# mega_shield.net
KiCad netlist of a schematic drawn in EAGLE
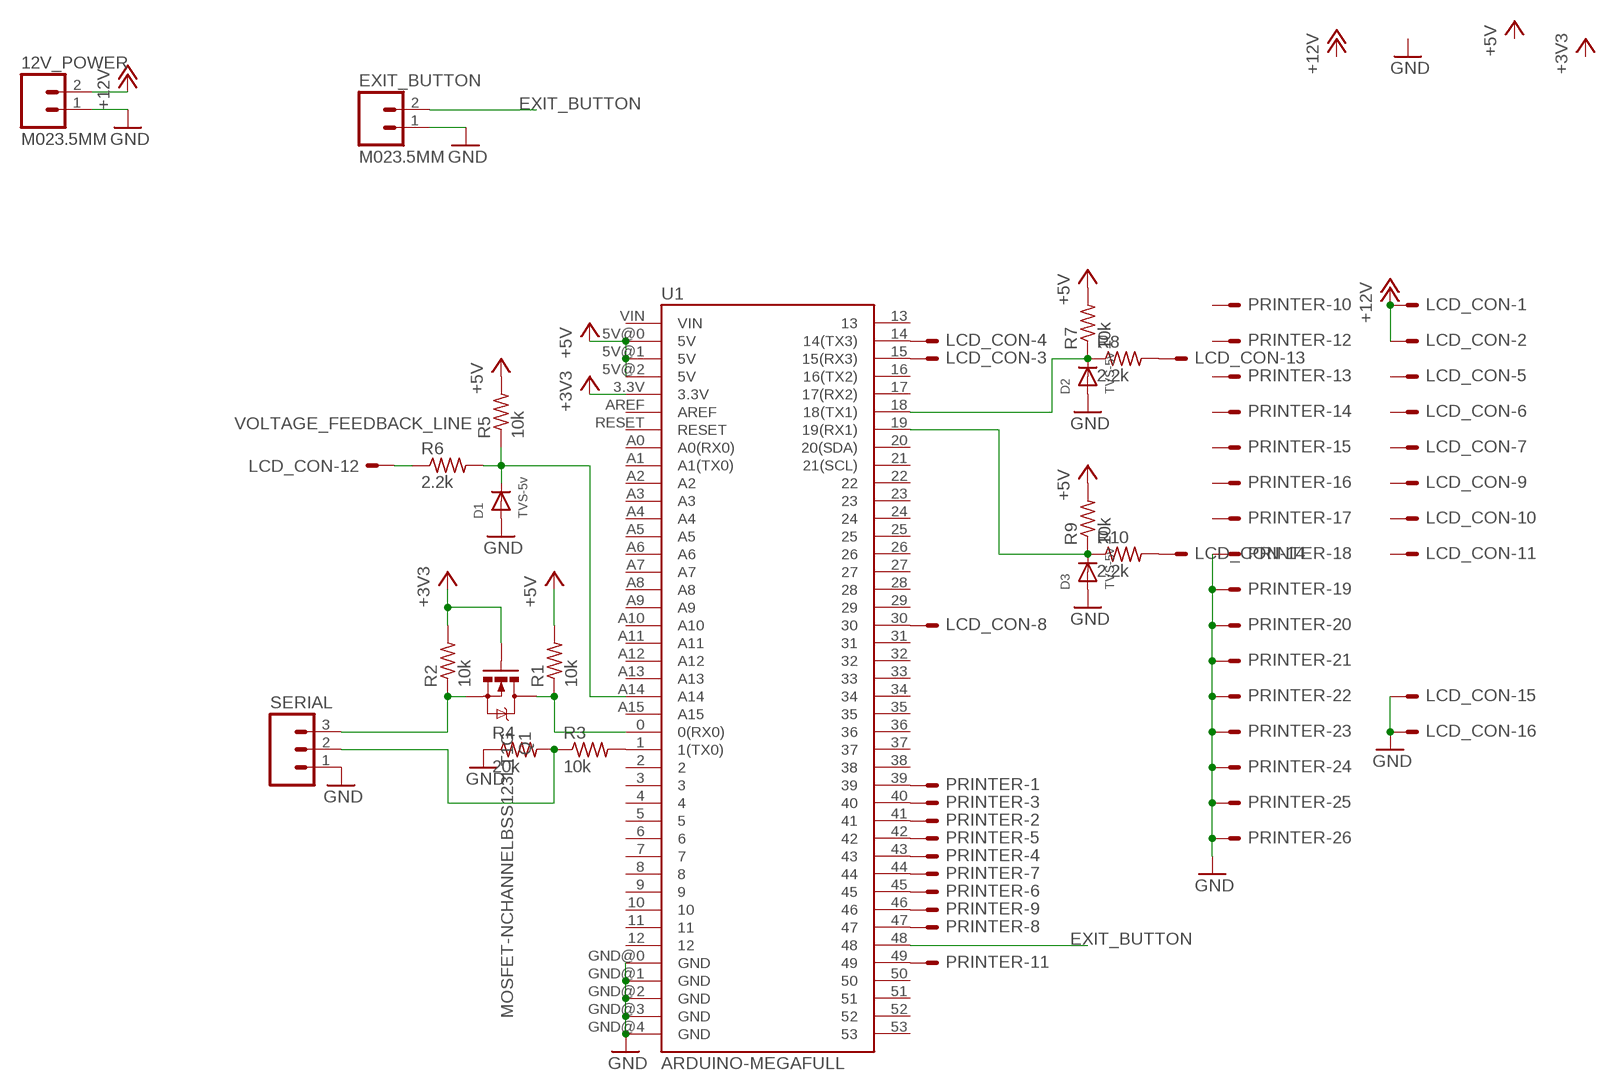
[diagram p0: schematic, sheet 1]

(export (version "E")
  (design (tool "Eeschema 10.0.6"))
  (components
    (comp (ref "12V_POWER")
      (value "M023.5MM")
      (footprint "eagle-import:SCREWTERMINAL-3.5MM-2")
      (libsource (lib "eagle-import") (part "M023.5MM"))
    )
    (comp (ref "D1")
      (value "TVS-5v")
      (footprint "eagle-import:SOD-123")
      (libsource (lib "eagle-import") (part "DIODESOD-123"))
    )
    (comp (ref "D2")
      (value "TVS-5v")
      (footprint "eagle-import:SOD-123")
      (libsource (lib "eagle-import") (part "DIODESOD-123"))
    )
    (comp (ref "D3")
      (value "TVS-5v")
      (footprint "eagle-import:SOD-123")
      (libsource (lib "eagle-import") (part "DIODESOD-123"))
    )
    (comp (ref "EXIT_BUTTON")
      (value "M023.5MM")
      (footprint "eagle-import:SCREWTERMINAL-3.5MM-2")
      (libsource (lib "eagle-import") (part "M023.5MM"))
    )
    (comp (ref "LCD_CON")
      (value "ML16E")
      (footprint "eagle-import:ML16")
      (libsource (lib "eagle-import") (part "ML16?E"))
    )
    (comp (ref "PRINTER")
      (value "ML26E")
      (footprint "eagle-import:ML26")
      (libsource (lib "eagle-import") (part "ML26?E"))
    )
    (comp (ref "Q1")
      (value "MOSFET-NCHANNELBSS123LT1G")
      (footprint "eagle-import:SOT23")
      (libsource (lib "eagle-import") (part "MOSFET-NCHANNELBSS123LT1G"))
    )
    (comp (ref "R1")
      (value "10k")
      (footprint "eagle-import:R0603")
      (libsource (lib "eagle-import") (part "R-US_R0603"))
    )
    (comp (ref "R2")
      (value "10k")
      (footprint "eagle-import:R0603")
      (libsource (lib "eagle-import") (part "R-US_R0603"))
    )
    (comp (ref "R3")
      (value "10k")
      (footprint "eagle-import:R0603")
      (libsource (lib "eagle-import") (part "R-US_R0603"))
    )
    (comp (ref "R4")
      (value "20k")
      (footprint "eagle-import:R0603")
      (libsource (lib "eagle-import") (part "R-US_R0603"))
    )
    (comp (ref "R5")
      (value "10k")
      (footprint "eagle-import:R0603")
      (libsource (lib "eagle-import") (part "R-US_R0603"))
    )
    (comp (ref "R6")
      (value "2.2k")
      (footprint "eagle-import:R0603")
      (libsource (lib "eagle-import") (part "R-US_R0603"))
    )
    (comp (ref "R7")
      (value "10k")
      (footprint "eagle-import:R0603")
      (libsource (lib "eagle-import") (part "R-US_R0603"))
    )
    (comp (ref "R8")
      (value "2.2k")
      (footprint "eagle-import:R0603")
      (libsource (lib "eagle-import") (part "R-US_R0603"))
    )
    (comp (ref "R9")
      (value "10k")
      (footprint "eagle-import:R0603")
      (libsource (lib "eagle-import") (part "R-US_R0603"))
    )
    (comp (ref "R10")
      (value "2.2k")
      (footprint "eagle-import:R0603")
      (libsource (lib "eagle-import") (part "R-US_R0603"))
    )
    (comp (ref "SERIAL")
      (value "M03SCREW")
      (footprint "eagle-import:SCREWTERMINAL-3.5MM-3")
      (libsource (lib "eagle-import") (part "M03SCREW"))
    )
    (comp (ref "U1")
      (value "ARDUINO-MEGAFULL")
      (footprint "eagle-import:ARDUINO_MEGA")
      (libsource (lib "eagle-import") (part "ARDUINO-MEGAFULL"))
    )
  )
  (nets
    (net (code "1") (name "+3V3") (class "Default")
      (node (ref "Q1") (pin "1") (pinfunction "G_1") (pintype "passive"))
      (node (ref "R2") (pin "2") (pinfunction "2_2") (pintype "passive"))
      (node (ref "U1") (pin "3.3V") (pinfunction "3.3V_3.3V") (pintype "bidirectional"))
    )
    (net (code "2") (name "+5V") (class "Default")
      (node (ref "R1") (pin "2") (pinfunction "2_2") (pintype "passive"))
      (node (ref "R5") (pin "2") (pinfunction "2_2") (pintype "passive"))
      (node (ref "R7") (pin "2") (pinfunction "2_2") (pintype "passive"))
      (node (ref "R9") (pin "2") (pinfunction "2_2") (pintype "passive"))
      (node (ref "U1") (pin "5V@0") (pinfunction "5V_5V@0") (pintype "bidirectional"))
      (node (ref "U1") (pin "5V@1") (pinfunction "5V_5V@1") (pintype "bidirectional"))
      (node (ref "U1") (pin "5V@2") (pinfunction "5V_5V@2") (pintype "bidirectional"))
    )
    (net (code "3") (name "+12V") (class "Default")
      (node (ref "12V_POWER") (pin "2") (pinfunction "2_2") (pintype "passive"))
      (node (ref "LCD_CON") (pin "1") (pinfunction "S_1") (pintype "passive"))
      (node (ref "LCD_CON") (pin "2") (pinfunction "S_2") (pintype "passive"))
    )
    (net (code "4") (name "/EXIT_BUTTON") (class "Default")
      (node (ref "EXIT_BUTTON") (pin "2") (pinfunction "2_2") (pintype "passive"))
      (node (ref "U1") (pin "48") (pinfunction "48_48") (pintype "bidirectional"))
    )
    (net (code "5") (name "/VOLTAGE_FEEDBACK_LINE") (class "Default")
      (node (ref "LCD_CON") (pin "12") (pinfunction "S_12") (pintype "passive"))
      (node (ref "R6") (pin "1") (pinfunction "1_1") (pintype "passive"))
    )
    (net (code "6") (name "GND") (class "Default")
      (node (ref "12V_POWER") (pin "1") (pinfunction "1_1") (pintype "passive"))
      (node (ref "D1") (pin "A") (pinfunction "A_A") (pintype "passive"))
      (node (ref "D2") (pin "A") (pinfunction "A_A") (pintype "passive"))
      (node (ref "D3") (pin "A") (pinfunction "A_A") (pintype "passive"))
      (node (ref "EXIT_BUTTON") (pin "1") (pinfunction "1_1") (pintype "passive"))
      (node (ref "LCD_CON") (pin "15") (pinfunction "S_15") (pintype "passive"))
      (node (ref "LCD_CON") (pin "16") (pinfunction "S_16") (pintype "passive"))
      (node (ref "PRINTER") (pin "18") (pinfunction "S_18") (pintype "passive"))
      (node (ref "PRINTER") (pin "19") (pinfunction "S_19") (pintype "passive"))
      (node (ref "PRINTER") (pin "20") (pinfunction "S_20") (pintype "passive"))
      (node (ref "PRINTER") (pin "21") (pinfunction "S_21") (pintype "passive"))
      (node (ref "PRINTER") (pin "22") (pinfunction "S_22") (pintype "passive"))
      (node (ref "PRINTER") (pin "23") (pinfunction "S_23") (pintype "passive"))
      (node (ref "PRINTER") (pin "24") (pinfunction "S_24") (pintype "passive"))
      (node (ref "PRINTER") (pin "25") (pinfunction "S_25") (pintype "passive"))
      (node (ref "PRINTER") (pin "26") (pinfunction "S_26") (pintype "passive"))
      (node (ref "R4") (pin "1") (pinfunction "1_1") (pintype "passive"))
      (node (ref "SERIAL") (pin "1") (pinfunction "1_1") (pintype "passive"))
      (node (ref "U1") (pin "GND@0") (pinfunction "GND_GND@0") (pintype "bidirectional"))
      (node (ref "U1") (pin "GND@1") (pinfunction "GND_GND@1") (pintype "bidirectional"))
      (node (ref "U1") (pin "GND@2") (pinfunction "GND_GND@2") (pintype "bidirectional"))
      (node (ref "U1") (pin "GND@3") (pinfunction "GND_GND@3") (pintype "bidirectional"))
      (node (ref "U1") (pin "GND@4") (pinfunction "GND_GND@4") (pintype "bidirectional"))
    )
    (net (code "7") (name "Net-(D1-PadC)") (class "Default")
      (node (ref "D1") (pin "C") (pinfunction "C_C") (pintype "passive"))
      (node (ref "R5") (pin "1") (pinfunction "1_1") (pintype "passive"))
      (node (ref "R6") (pin "2") (pinfunction "2_2") (pintype "passive"))
      (node (ref "U1") (pin "A14") (pinfunction "A14_A14") (pintype "bidirectional"))
    )
    (net (code "8") (name "Net-(LCD_CONE-S)") (class "Default")
      (node (ref "LCD_CON") (pin "13") (pinfunction "S_13") (pintype "passive"))
      (node (ref "R8") (pin "2") (pinfunction "2_2") (pintype "passive"))
    )
    (net (code "9") (name "Net-(LCD_CONF-S)") (class "Default")
      (node (ref "LCD_CON") (pin "14") (pinfunction "S_14") (pintype "passive"))
      (node (ref "R10") (pin "2") (pinfunction "2_2") (pintype "passive"))
    )
    (net (code "10") (name "Net-(LCD_CONJ-S)") (class "Default")
      (node (ref "LCD_CON") (pin "3") (pinfunction "S_3") (pintype "passive"))
      (node (ref "U1") (pin "15") (pinfunction "15(RX3)_15") (pintype "bidirectional"))
    )
    (net (code "11") (name "Net-(LCD_CONK-S)") (class "Default")
      (node (ref "LCD_CON") (pin "4") (pinfunction "S_4") (pintype "passive"))
      (node (ref "U1") (pin "14") (pinfunction "14(TX3)_14") (pintype "bidirectional"))
    )
    (net (code "12") (name "Net-(LCD_CONO-S)") (class "Default")
      (node (ref "LCD_CON") (pin "8") (pinfunction "S_8") (pintype "passive"))
      (node (ref "U1") (pin "30") (pinfunction "30_30") (pintype "bidirectional"))
    )
    (net (code "13") (name "Net-(PRINTERA-S)") (class "Default")
      (node (ref "PRINTER") (pin "1") (pinfunction "S_1") (pintype "passive"))
      (node (ref "U1") (pin "39") (pinfunction "39_39") (pintype "bidirectional"))
    )
    (net (code "14") (name "Net-(PRINTERC-S)") (class "Default")
      (node (ref "PRINTER") (pin "11") (pinfunction "S_11") (pintype "passive"))
      (node (ref "U1") (pin "49") (pinfunction "49_49") (pintype "bidirectional"))
    )
    (net (code "15") (name "Net-(PRINTERL-S)") (class "Default")
      (node (ref "PRINTER") (pin "2") (pinfunction "S_2") (pintype "passive"))
      (node (ref "U1") (pin "41") (pinfunction "41_41") (pintype "bidirectional"))
    )
    (net (code "16") (name "Net-(PRINTERT-S)") (class "Default")
      (node (ref "PRINTER") (pin "3") (pinfunction "S_3") (pintype "passive"))
      (node (ref "U1") (pin "40") (pinfunction "40_40") (pintype "bidirectional"))
    )
    (net (code "17") (name "Net-(PRINTERU-S)") (class "Default")
      (node (ref "PRINTER") (pin "4") (pinfunction "S_4") (pintype "passive"))
      (node (ref "U1") (pin "43") (pinfunction "43_43") (pintype "bidirectional"))
    )
    (net (code "18") (name "Net-(PRINTERV-S)") (class "Default")
      (node (ref "PRINTER") (pin "5") (pinfunction "S_5") (pintype "passive"))
      (node (ref "U1") (pin "42") (pinfunction "42_42") (pintype "bidirectional"))
    )
    (net (code "19") (name "Net-(PRINTERW-S)") (class "Default")
      (node (ref "PRINTER") (pin "6") (pinfunction "S_6") (pintype "passive"))
      (node (ref "U1") (pin "45") (pinfunction "45_45") (pintype "bidirectional"))
    )
    (net (code "20") (name "Net-(PRINTERX-S)") (class "Default")
      (node (ref "PRINTER") (pin "7") (pinfunction "S_7") (pintype "passive"))
      (node (ref "U1") (pin "44") (pinfunction "44_44") (pintype "bidirectional"))
    )
    (net (code "21") (name "Net-(PRINTERY-S)") (class "Default")
      (node (ref "PRINTER") (pin "8") (pinfunction "S_8") (pintype "passive"))
      (node (ref "U1") (pin "47") (pinfunction "47_47") (pintype "bidirectional"))
    )
    (net (code "22") (name "Net-(PRINTERZ-S)") (class "Default")
      (node (ref "PRINTER") (pin "9") (pinfunction "S_9") (pintype "passive"))
      (node (ref "U1") (pin "46") (pinfunction "46_46") (pintype "bidirectional"))
    )
    (net (code "23") (name "Net-(Q1-D)") (class "Default")
      (node (ref "Q1") (pin "3") (pinfunction "D_3") (pintype "passive"))
      (node (ref "R1") (pin "1") (pinfunction "1_1") (pintype "passive"))
      (node (ref "U1") (pin "0") (pinfunction "0(RX0)_0") (pintype "bidirectional"))
    )
    (net (code "24") (name "Net-(Q1-S)") (class "Default")
      (node (ref "Q1") (pin "2") (pinfunction "S_2") (pintype "passive"))
      (node (ref "R2") (pin "1") (pinfunction "1_1") (pintype "passive"))
      (node (ref "SERIAL") (pin "3") (pinfunction "3_3") (pintype "passive"))
    )
    (net (code "25") (name "Net-(R3-Pad1)") (class "Default")
      (node (ref "R3") (pin "1") (pinfunction "1_1") (pintype "passive"))
      (node (ref "R4") (pin "2") (pinfunction "2_2") (pintype "passive"))
      (node (ref "SERIAL") (pin "2") (pinfunction "2_2") (pintype "passive"))
    )
    (net (code "26") (name "Net-(U1-1(TX0))") (class "Default")
      (node (ref "R3") (pin "2") (pinfunction "2_2") (pintype "passive"))
      (node (ref "U1") (pin "1") (pinfunction "1(TX0)_1") (pintype "bidirectional"))
    )
    (net (code "27") (name "Net-(U1-18(TX1))") (class "Default")
      (node (ref "D2") (pin "C") (pinfunction "C_C") (pintype "passive"))
      (node (ref "R7") (pin "1") (pinfunction "1_1") (pintype "passive"))
      (node (ref "R8") (pin "1") (pinfunction "1_1") (pintype "passive"))
      (node (ref "U1") (pin "18") (pinfunction "18(TX1)_18") (pintype "bidirectional"))
    )
    (net (code "28") (name "Net-(U1-19(RX1))") (class "Default")
      (node (ref "D3") (pin "C") (pinfunction "C_C") (pintype "passive"))
      (node (ref "R10") (pin "1") (pinfunction "1_1") (pintype "passive"))
      (node (ref "R9") (pin "1") (pinfunction "1_1") (pintype "passive"))
      (node (ref "U1") (pin "19") (pinfunction "19(RX1)_19") (pintype "bidirectional"))
    )
    (net (code "29") (name "unconnected-(LCD_CONB-S-Pad10)") (class "Default")
      (node (ref "LCD_CON") (pin "10") (pinfunction "S_10") (pintype "passive"))
    )
    (net (code "30") (name "unconnected-(LCD_CONC-S-Pad11)") (class "Default")
      (node (ref "LCD_CON") (pin "11") (pinfunction "S_11") (pintype "passive"))
    )
    (net (code "31") (name "unconnected-(LCD_CONL-S-Pad5)") (class "Default")
      (node (ref "LCD_CON") (pin "5") (pinfunction "S_5") (pintype "passive"))
    )
    (net (code "32") (name "unconnected-(LCD_CONM-S-Pad6)") (class "Default")
      (node (ref "LCD_CON") (pin "6") (pinfunction "S_6") (pintype "passive"))
    )
    (net (code "33") (name "unconnected-(LCD_CONN-S-Pad7)") (class "Default")
      (node (ref "LCD_CON") (pin "7") (pinfunction "S_7") (pintype "passive"))
    )
    (net (code "34") (name "unconnected-(LCD_CONP-S-Pad9)") (class "Default")
      (node (ref "LCD_CON") (pin "9") (pinfunction "S_9") (pintype "passive"))
    )
    (net (code "35") (name "unconnected-(PRINTERB-S-Pad10)") (class "Default")
      (node (ref "PRINTER") (pin "10") (pinfunction "S_10") (pintype "passive"))
    )
    (net (code "36") (name "unconnected-(PRINTERD-S-Pad12)") (class "Default")
      (node (ref "PRINTER") (pin "12") (pinfunction "S_12") (pintype "passive"))
    )
    (net (code "37") (name "unconnected-(PRINTERE-S-Pad13)") (class "Default")
      (node (ref "PRINTER") (pin "13") (pinfunction "S_13") (pintype "passive"))
    )
    (net (code "38") (name "unconnected-(PRINTERF-S-Pad14)") (class "Default")
      (node (ref "PRINTER") (pin "14") (pinfunction "S_14") (pintype "passive"))
    )
    (net (code "39") (name "unconnected-(PRINTERG-S-Pad15)") (class "Default")
      (node (ref "PRINTER") (pin "15") (pinfunction "S_15") (pintype "passive"))
    )
    (net (code "40") (name "unconnected-(PRINTERH-S-Pad16)") (class "Default")
      (node (ref "PRINTER") (pin "16") (pinfunction "S_16") (pintype "passive"))
    )
    (net (code "41") (name "unconnected-(PRINTERI-S-Pad17)") (class "Default")
      (node (ref "PRINTER") (pin "17") (pinfunction "S_17") (pintype "passive"))
    )
    (net (code "42") (name "unconnected-(U1-16(TX2)-Pad16)") (class "Default")
      (node (ref "U1") (pin "16") (pinfunction "16(TX2)_16") (pintype "bidirectional"))
    )
    (net (code "43") (name "unconnected-(U1-17(RX2)-Pad17)") (class "Default")
      (node (ref "U1") (pin "17") (pinfunction "17(RX2)_17") (pintype "bidirectional"))
    )
    (net (code "44") (name "unconnected-(U1-20(SDA)-Pad20)") (class "Default")
      (node (ref "U1") (pin "20") (pinfunction "20(SDA)_20") (pintype "bidirectional"))
    )
    (net (code "45") (name "unconnected-(U1-21(SCL)-Pad21)") (class "Default")
      (node (ref "U1") (pin "21") (pinfunction "21(SCL)_21") (pintype "bidirectional"))
    )
    (net (code "46") (name "unconnected-(U1-A0(RX0)-PadA0)") (class "Default")
      (node (ref "U1") (pin "A0") (pinfunction "A0(RX0)_A0") (pintype "bidirectional"))
    )
    (net (code "47") (name "unconnected-(U1-A1(TX0)-PadA1)") (class "Default")
      (node (ref "U1") (pin "A1") (pinfunction "A1(TX0)_A1") (pintype "bidirectional"))
    )
    (net (code "48") (name "unconnected-(U1-Pad2)") (class "Default")
      (node (ref "U1") (pin "2") (pinfunction "2_2") (pintype "bidirectional"))
    )
    (net (code "49") (name "unconnected-(U1-Pad3)") (class "Default")
      (node (ref "U1") (pin "3") (pinfunction "3_3") (pintype "bidirectional"))
    )
    (net (code "50") (name "unconnected-(U1-Pad4)") (class "Default")
      (node (ref "U1") (pin "4") (pinfunction "4_4") (pintype "bidirectional"))
    )
    (net (code "51") (name "unconnected-(U1-Pad5)") (class "Default")
      (node (ref "U1") (pin "5") (pinfunction "5_5") (pintype "bidirectional"))
    )
    (net (code "52") (name "unconnected-(U1-Pad6)") (class "Default")
      (node (ref "U1") (pin "6") (pinfunction "6_6") (pintype "bidirectional"))
    )
    (net (code "53") (name "unconnected-(U1-Pad7)") (class "Default")
      (node (ref "U1") (pin "7") (pinfunction "7_7") (pintype "bidirectional"))
    )
    (net (code "54") (name "unconnected-(U1-Pad8)") (class "Default")
      (node (ref "U1") (pin "8") (pinfunction "8_8") (pintype "bidirectional"))
    )
    (net (code "55") (name "unconnected-(U1-Pad9)") (class "Default")
      (node (ref "U1") (pin "9") (pinfunction "9_9") (pintype "bidirectional"))
    )
    (net (code "56") (name "unconnected-(U1-Pad10)") (class "Default")
      (node (ref "U1") (pin "10") (pinfunction "10_10") (pintype "bidirectional"))
    )
    (net (code "57") (name "unconnected-(U1-Pad11)") (class "Default")
      (node (ref "U1") (pin "11") (pinfunction "11_11") (pintype "bidirectional"))
    )
    (net (code "58") (name "unconnected-(U1-Pad12)") (class "Default")
      (node (ref "U1") (pin "12") (pinfunction "12_12") (pintype "bidirectional"))
    )
    (net (code "59") (name "unconnected-(U1-Pad13)") (class "Default")
      (node (ref "U1") (pin "13") (pinfunction "13_13") (pintype "bidirectional"))
    )
    (net (code "60") (name "unconnected-(U1-Pad22)") (class "Default")
      (node (ref "U1") (pin "22") (pinfunction "22_22") (pintype "bidirectional"))
    )
    (net (code "61") (name "unconnected-(U1-Pad23)") (class "Default")
      (node (ref "U1") (pin "23") (pinfunction "23_23") (pintype "bidirectional"))
    )
    (net (code "62") (name "unconnected-(U1-Pad24)") (class "Default")
      (node (ref "U1") (pin "24") (pinfunction "24_24") (pintype "bidirectional"))
    )
    (net (code "63") (name "unconnected-(U1-Pad25)") (class "Default")
      (node (ref "U1") (pin "25") (pinfunction "25_25") (pintype "bidirectional"))
    )
    (net (code "64") (name "unconnected-(U1-Pad26)") (class "Default")
      (node (ref "U1") (pin "26") (pinfunction "26_26") (pintype "bidirectional"))
    )
    (net (code "65") (name "unconnected-(U1-Pad27)") (class "Default")
      (node (ref "U1") (pin "27") (pinfunction "27_27") (pintype "bidirectional"))
    )
    (net (code "66") (name "unconnected-(U1-Pad28)") (class "Default")
      (node (ref "U1") (pin "28") (pinfunction "28_28") (pintype "bidirectional"))
    )
    (net (code "67") (name "unconnected-(U1-Pad29)") (class "Default")
      (node (ref "U1") (pin "29") (pinfunction "29_29") (pintype "bidirectional"))
    )
    (net (code "68") (name "unconnected-(U1-Pad31)") (class "Default")
      (node (ref "U1") (pin "31") (pinfunction "31_31") (pintype "bidirectional"))
    )
    (net (code "69") (name "unconnected-(U1-Pad32)") (class "Default")
      (node (ref "U1") (pin "32") (pinfunction "32_32") (pintype "bidirectional"))
    )
    (net (code "70") (name "unconnected-(U1-Pad33)") (class "Default")
      (node (ref "U1") (pin "33") (pinfunction "33_33") (pintype "bidirectional"))
    )
    (net (code "71") (name "unconnected-(U1-Pad34)") (class "Default")
      (node (ref "U1") (pin "34") (pinfunction "34_34") (pintype "bidirectional"))
    )
    (net (code "72") (name "unconnected-(U1-Pad35)") (class "Default")
      (node (ref "U1") (pin "35") (pinfunction "35_35") (pintype "bidirectional"))
    )
    (net (code "73") (name "unconnected-(U1-Pad36)") (class "Default")
      (node (ref "U1") (pin "36") (pinfunction "36_36") (pintype "bidirectional"))
    )
    (net (code "74") (name "unconnected-(U1-Pad37)") (class "Default")
      (node (ref "U1") (pin "37") (pinfunction "37_37") (pintype "bidirectional"))
    )
    (net (code "75") (name "unconnected-(U1-Pad38)") (class "Default")
      (node (ref "U1") (pin "38") (pinfunction "38_38") (pintype "bidirectional"))
    )
    (net (code "76") (name "unconnected-(U1-Pad50)") (class "Default")
      (node (ref "U1") (pin "50") (pinfunction "50_50") (pintype "bidirectional"))
    )
    (net (code "77") (name "unconnected-(U1-Pad51)") (class "Default")
      (node (ref "U1") (pin "51") (pinfunction "51_51") (pintype "bidirectional"))
    )
    (net (code "78") (name "unconnected-(U1-Pad52)") (class "Default")
      (node (ref "U1") (pin "52") (pinfunction "52_52") (pintype "bidirectional"))
    )
    (net (code "79") (name "unconnected-(U1-Pad53)") (class "Default")
      (node (ref "U1") (pin "53") (pinfunction "53_53") (pintype "bidirectional"))
    )
    (net (code "80") (name "unconnected-(U1-PadA2)") (class "Default")
      (node (ref "U1") (pin "A2") (pinfunction "A2_A2") (pintype "bidirectional"))
    )
    (net (code "81") (name "unconnected-(U1-PadA3)") (class "Default")
      (node (ref "U1") (pin "A3") (pinfunction "A3_A3") (pintype "bidirectional"))
    )
    (net (code "82") (name "unconnected-(U1-PadA4)") (class "Default")
      (node (ref "U1") (pin "A4") (pinfunction "A4_A4") (pintype "bidirectional"))
    )
    (net (code "83") (name "unconnected-(U1-PadA5)") (class "Default")
      (node (ref "U1") (pin "A5") (pinfunction "A5_A5") (pintype "bidirectional"))
    )
    (net (code "84") (name "unconnected-(U1-PadA6)") (class "Default")
      (node (ref "U1") (pin "A6") (pinfunction "A6_A6") (pintype "bidirectional"))
    )
    (net (code "85") (name "unconnected-(U1-PadA7)") (class "Default")
      (node (ref "U1") (pin "A7") (pinfunction "A7_A7") (pintype "bidirectional"))
    )
    (net (code "86") (name "unconnected-(U1-PadA8)") (class "Default")
      (node (ref "U1") (pin "A8") (pinfunction "A8_A8") (pintype "bidirectional"))
    )
    (net (code "87") (name "unconnected-(U1-PadA9)") (class "Default")
      (node (ref "U1") (pin "A9") (pinfunction "A9_A9") (pintype "bidirectional"))
    )
    (net (code "88") (name "unconnected-(U1-PadA10)") (class "Default")
      (node (ref "U1") (pin "A10") (pinfunction "A10_A10") (pintype "bidirectional"))
    )
    (net (code "89") (name "unconnected-(U1-PadA11)") (class "Default")
      (node (ref "U1") (pin "A11") (pinfunction "A11_A11") (pintype "bidirectional"))
    )
    (net (code "90") (name "unconnected-(U1-PadA12)") (class "Default")
      (node (ref "U1") (pin "A12") (pinfunction "A12_A12") (pintype "bidirectional"))
    )
    (net (code "91") (name "unconnected-(U1-PadA13)") (class "Default")
      (node (ref "U1") (pin "A13") (pinfunction "A13_A13") (pintype "bidirectional"))
    )
    (net (code "92") (name "unconnected-(U1-PadA15)") (class "Default")
      (node (ref "U1") (pin "A15") (pinfunction "A15_A15") (pintype "bidirectional"))
    )
    (net (code "93") (name "unconnected-(U1-PadAREF)") (class "Default")
      (node (ref "U1") (pin "AREF") (pinfunction "AREF_AREF") (pintype "bidirectional"))
    )
    (net (code "94") (name "unconnected-(U1-PadRESET)") (class "Default")
      (node (ref "U1") (pin "RESET") (pinfunction "RESET_RESET") (pintype "bidirectional"))
    )
    (net (code "95") (name "unconnected-(U1-PadVIN)") (class "Default")
      (node (ref "U1") (pin "VIN") (pinfunction "VIN_VIN") (pintype "bidirectional"))
    )
  )
)
